# M.net
KiCad netlist of a schematic drawn in Altium Designer
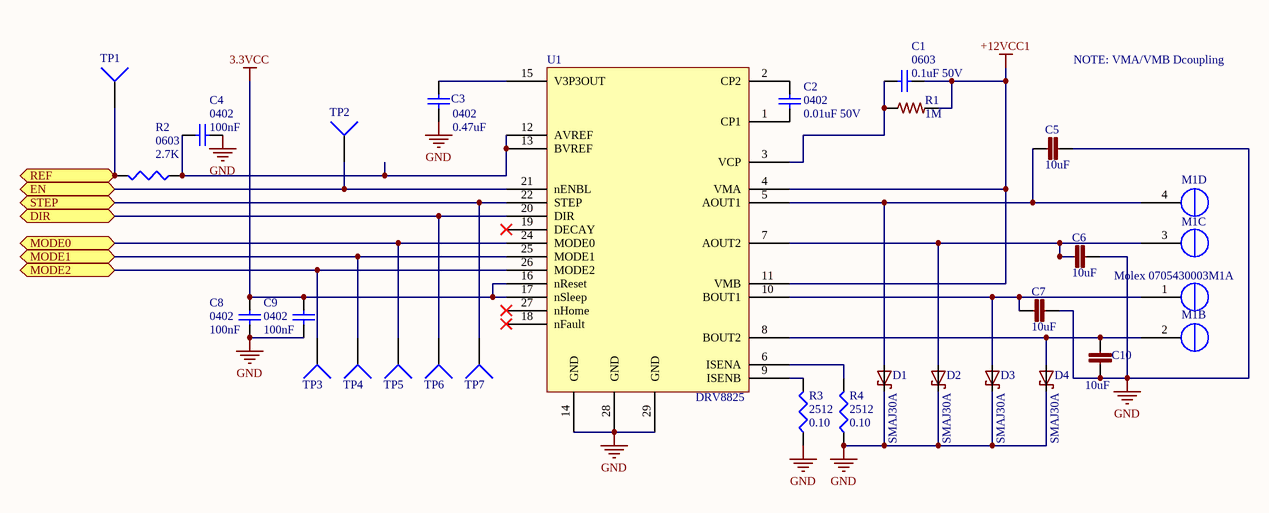
[diagram p0: M.SchDoc]

(export (version "E")
  (design (tool "Eeschema 10.0.6"))
  (components
    (comp (ref "C1")
      (value "0603")
      (footprint "1608[0603]")
      (description "Capacitor (Semiconductor SIM Model)")
      (fields (field (name "ALTIUM_VALUE") "0.1uF 50V") (field (name "PUBLISHER") "Altium Limited"))
      (libsource (lib "Miscellaneous Devices") (part "Cap Semi"))
    )
    (comp (ref "C2")
      (value "0.01uF 50V")
      (footprint "C0402")
      (description "CAP CER 10000PF 50V X7R 0402")
      (fields
        (field (name "MFR PART #") "GRM155R71H103JA88D")
        (field (name "MFR") "Murata")
        (field (name "PACKAGEREFERENCE") "0402")
        (field (name "PUBLISHER") "Ultimachine")
      )
      (libsource (lib "Tigershark3D") (part "GRM155R71H103JA88D"))
    )
    (comp (ref "C3")
      (value "0.47uF")
      (footprint "C0402")
      (description "0.47uF 6.3v C0402 - GRM155R60J474KE19D")
      (fields
        (field (name "MFR PART #") "GRM155R60J474KE19D")
        (field (name "MFR") "Murata")
        (field (name "PACKAGEREFERENCE") "0402")
        (field (name "PUBLISHER") "Ultimachine")
      )
      (libsource (lib "Tigershark3D") (part "GRM155R60J474KE19D"))
    )
    (comp (ref "C4")
      (value "100nF")
      (footprint "C0402")
      (description "Capacitor (Semiconductor SIM Model)")
      (fields
        (field (name "MFR PART #") "GRM155R71C104KA88D")
        (field (name "MFR") "Murata")
        (field (name "PACKAGEREFERENCE") "0402")
        (field (name "PUBLISHER") "Ultimachine")
      )
      (libsource (lib "Tigershark3D") (part "100nF C0402 - GRM155R71C104KA88D"))
    )
    (comp (ref "C5")
      (value "10uF")
      (footprint "C0603")
      (description "CAP CER 0603 1uF 10V Y5V")
      (fields
        (field (name "MANUFACTURERPARTNUMBER") "CC0603ZRY5V6BB105")
        (field (name "PUBLISHER") "UltiMachine")
      )
      (libsource (lib "Tigershark3D") (part "CC0603ZRY5V6BB105"))
    )
    (comp (ref "C6")
      (value "10uF")
      (footprint "C0603")
      (description "CAP CER 0603 1uF 10V Y5V")
      (fields
        (field (name "MANUFACTURERPARTNUMBER") "CC0603ZRY5V6BB105")
        (field (name "PUBLISHER") "UltiMachine")
      )
      (libsource (lib "Tigershark3D") (part "CC0603ZRY5V6BB105"))
    )
    (comp (ref "C7")
      (value "10uF")
      (footprint "C0603")
      (description "CAP CER 0603 1uF 10V Y5V")
      (fields
        (field (name "MANUFACTURERPARTNUMBER") "CC0603ZRY5V6BB105")
        (field (name "PUBLISHER") "UltiMachine")
      )
      (libsource (lib "Tigershark3D") (part "CC0603ZRY5V6BB105"))
    )
    (comp (ref "C8")
      (value "100nF")
      (footprint "C0402")
      (description "Capacitor (Semiconductor SIM Model)")
      (fields
        (field (name "MFR PART #") "GRM155R71C104KA88D")
        (field (name "MFR") "Murata")
        (field (name "PACKAGEREFERENCE") "0402")
        (field (name "PUBLISHER") "Ultimachine")
      )
      (libsource (lib "Tigershark3D") (part "100nF C0402 - GRM155R71C104KA88D"))
    )
    (comp (ref "C9")
      (value "100nF")
      (footprint "C0402")
      (description "Capacitor (Semiconductor SIM Model)")
      (fields
        (field (name "MFR PART #") "GRM155R71C104KA88D")
        (field (name "MFR") "Murata")
        (field (name "PACKAGEREFERENCE") "0402")
        (field (name "PUBLISHER") "Ultimachine")
      )
      (libsource (lib "Tigershark3D") (part "100nF C0402 - GRM155R71C104KA88D"))
    )
    (comp (ref "C10")
      (value "10uF")
      (footprint "C0603")
      (description "CAP CER 0603 1uF 10V Y5V")
      (fields
        (field (name "MANUFACTURERPARTNUMBER") "CC0603ZRY5V6BB105")
        (field (name "PUBLISHER") "UltiMachine")
      )
      (libsource (lib "") (part "CC0603ZRY5V6BB105_1"))
    )
    (comp (ref "D1")
      (value "SMAJ30A")
      (footprint "SMA-SM")
      (description "DIODE TVS 30V SMA")
      (fields (field (name "PUBLISHER") "UltiMachine"))
      (libsource (lib "Tigershark3D") (part "SMAJ30A"))
    )
    (comp (ref "D2")
      (value "SMAJ30A")
      (footprint "SMA-SM")
      (description "DIODE TVS 30V SMA")
      (fields (field (name "PUBLISHER") "UltiMachine"))
      (libsource (lib "Tigershark3D") (part "SMAJ30A"))
    )
    (comp (ref "D3")
      (value "SMAJ30A")
      (footprint "SMA-SM")
      (description "DIODE TVS 30V SMA")
      (fields (field (name "PUBLISHER") "UltiMachine"))
      (libsource (lib "Tigershark3D") (part "SMAJ30A"))
    )
    (comp (ref "D4")
      (value "SMAJ30A")
      (footprint "SMA-SM")
      (description "DIODE TVS 30V SMA")
      (fields (field (name "PUBLISHER") "UltiMachine"))
      (libsource (lib "Tigershark3D") (part "SMAJ30A"))
    )
    (comp (ref "M1")
      (value "Molex 0705430003")
      (footprint "4POL254")
      (description "Molex 4 Pin Clip Connector")
      (libsource (lib "ZMBo Schematic Library") (part "Molex 0705430003 Alt"))
    )
    (comp (ref "R1")
      (value "1M")
      (footprint "R0402")
      (description "RES 0402 1M 100mW 5%")
      (fields (field (name "MANUFACTURERPARTNUMBER") "ERJ2GEJ105X") (field (name "PUBLISHER") "UltiMachine"))
      (libsource (lib "Tigershark3D") (part "ERJ2GEJ105X"))
    )
    (comp (ref "R2")
      (value "0603")
      (footprint "J1-0603")
      (description "Resistor")
      (fields (field (name "ALTIUM_VALUE") "2.7K") (field (name "PUBLISHER") "Altium Limited"))
      (libsource (lib "Miscellaneous Devices") (part "Res3"))
    )
    (comp (ref "R3")
      (value "2512")
      (footprint "Resistor2512")
      (description "Resistor")
      (fields (field (name "ALTIUM_VALUE") "0.10") (field (name "PUBLISHER") "Altium Limited"))
      (libsource (lib "Miscellaneous Devices") (part "Res3"))
    )
    (comp (ref "R4")
      (value "2512")
      (footprint "Resistor2512")
      (description "Resistor")
      (fields (field (name "ALTIUM_VALUE") "0.10") (field (name "PUBLISHER") "Altium Limited"))
      (libsource (lib "Miscellaneous Devices") (part "Res3"))
    )
    (comp (ref "TP1")
      (value "TP4")
      (footprint "TP-2")
      (description "Socket")
      (fields (field (name "PUBLISHER") "Altium Limited"))
      (libsource (lib "ZMBo Schematic Library") (part "Socket"))
    )
    (comp (ref "TP2")
      (value "TP4")
      (footprint "TP-2")
      (description "Socket")
      (fields (field (name "PUBLISHER") "Altium Limited"))
      (libsource (lib "ZMBo Schematic Library") (part "Socket"))
    )
    (comp (ref "TP3")
      (value "TP4")
      (footprint "TP-2")
      (description "Socket")
      (fields (field (name "PUBLISHER") "Altium Limited"))
      (libsource (lib "ZMBo Schematic Library") (part "Socket"))
    )
    (comp (ref "TP4")
      (value "TP4")
      (footprint "TP-2")
      (description "Socket")
      (fields (field (name "PUBLISHER") "Altium Limited"))
      (libsource (lib "ZMBo Schematic Library") (part "Socket"))
    )
    (comp (ref "TP5")
      (value "TP4")
      (footprint "TP-2")
      (description "Socket")
      (fields (field (name "PUBLISHER") "Altium Limited"))
      (libsource (lib "ZMBo Schematic Library") (part "Socket"))
    )
    (comp (ref "TP6")
      (value "TP4")
      (footprint "TP-2")
      (description "Socket")
      (fields (field (name "PUBLISHER") "Altium Limited"))
      (libsource (lib "ZMBo Schematic Library") (part "Socket"))
    )
    (comp (ref "TP7")
      (value "TP4")
      (footprint "TP-2")
      (description "Socket")
      (fields (field (name "PUBLISHER") "Altium Limited"))
      (libsource (lib "ZMBo Schematic Library") (part "Socket"))
    )
    (comp (ref "U1")
      (value "DRV8825")
      (footprint "DRV8825")
      (description "DRV8825 Ti Stepper Driver")
      (libsource (lib "ZMBo Schematic Library") (part "DRV8825"))
    )
  )
  (nets
    (net (code "1") (name "+12VCC1") (class "Default")
      (node (ref "C1") (pin "1") (pinfunction "1_1") (pintype "passive"))
      (node (ref "R1") (pin "2") (pinfunction "2_2") (pintype "passive"))
      (node (ref "U1") (pin "11") (pinfunction "VMB_11") (pintype "passive"))
      (node (ref "U1") (pin "4") (pinfunction "VMA_4") (pintype "passive"))
    )
    (net (code "2") (name "/DIR") (class "Default")
      (node (ref "TP6") (pin "1") (pinfunction "1_1") (pintype "passive"))
      (node (ref "U1") (pin "20") (pinfunction "DIR_20") (pintype "passive"))
    )
    (net (code "3") (name "/EN") (class "Default")
      (node (ref "TP2") (pin "1") (pinfunction "1_1") (pintype "passive"))
      (node (ref "U1") (pin "21") (pinfunction "nENBL_21") (pintype "passive"))
    )
    (net (code "4") (name "/MODE0") (class "Default")
      (node (ref "TP5") (pin "1") (pinfunction "1_1") (pintype "passive"))
      (node (ref "U1") (pin "24") (pinfunction "MODE0_24") (pintype "passive"))
    )
    (net (code "5") (name "/MODE1") (class "Default")
      (node (ref "TP4") (pin "1") (pinfunction "1_1") (pintype "passive"))
      (node (ref "U1") (pin "25") (pinfunction "MODE1_25") (pintype "passive"))
    )
    (net (code "6") (name "/MODE2") (class "Default")
      (node (ref "TP3") (pin "1") (pinfunction "1_1") (pintype "passive"))
      (node (ref "U1") (pin "26") (pinfunction "MODE2_26") (pintype "passive"))
    )
    (net (code "7") (name "/REF") (class "Default")
      (node (ref "R2") (pin "2") (pinfunction "2_2") (pintype "passive"))
      (node (ref "TP1") (pin "1") (pinfunction "1_1") (pintype "passive"))
    )
    (net (code "8") (name "/STEP") (class "Default")
      (node (ref "TP7") (pin "1") (pinfunction "1_1") (pintype "passive"))
      (node (ref "U1") (pin "22") (pinfunction "STEP_22") (pintype "passive"))
    )
    (net (code "9") (name "3.3VCC") (class "Default")
      (node (ref "C8") (pin "2") (pinfunction "2_2") (pintype "passive"))
      (node (ref "C9") (pin "2") (pinfunction "2_2") (pintype "passive"))
      (node (ref "U1") (pin "16") (pinfunction "nReset_16") (pintype "passive"))
      (node (ref "U1") (pin "17") (pinfunction "nSleep_17") (pintype "passive"))
    )
    (net (code "10") (name "GND") (class "Default")
      (node (ref "C10") (pin "2") (pinfunction "2_2") (pintype "passive"))
      (node (ref "C3") (pin "1") (pinfunction "1_1") (pintype "passive"))
      (node (ref "C4") (pin "1") (pinfunction "1_1") (pintype "passive"))
      (node (ref "C5") (pin "2") (pinfunction "2_2") (pintype "passive"))
      (node (ref "C6") (pin "2") (pinfunction "2_2") (pintype "passive"))
      (node (ref "C7") (pin "2") (pinfunction "2_2") (pintype "passive"))
      (node (ref "C8") (pin "1") (pinfunction "1_1") (pintype "passive"))
      (node (ref "C9") (pin "1") (pinfunction "1_1") (pintype "passive"))
      (node (ref "D1") (pin "C") (pinfunction "C_C") (pintype "passive"))
      (node (ref "D2") (pin "C") (pinfunction "C_C") (pintype "passive"))
      (node (ref "D3") (pin "C") (pinfunction "C_C") (pintype "passive"))
      (node (ref "D4") (pin "C") (pinfunction "C_C") (pintype "passive"))
      (node (ref "R3") (pin "1") (pinfunction "1_1") (pintype "passive"))
      (node (ref "R4") (pin "1") (pinfunction "1_1") (pintype "passive"))
      (node (ref "U1") (pin "14") (pinfunction "GND_14") (pintype "passive"))
      (node (ref "U1") (pin "28") (pinfunction "GND_28") (pintype "passive"))
      (node (ref "U1") (pin "29") (pinfunction "GND_29") (pintype "passive"))
    )
    (net (code "11") (name "Net-(M1A-OUT2B)") (class "Default")
      (node (ref "C7") (pin "1") (pinfunction "1_1") (pintype "passive"))
      (node (ref "D3") (pin "A") (pinfunction "A_A") (pintype "passive"))
      (node (ref "M1") (pin "1") (pinfunction "OUT2B_1") (pintype "passive"))
      (node (ref "U1") (pin "10") (pinfunction "BOUT1_10") (pintype "passive"))
    )
    (net (code "12") (name "Net-(M1B-OUT2A)") (class "Default")
      (node (ref "C10") (pin "1") (pinfunction "1_1") (pintype "passive"))
      (node (ref "D4") (pin "A") (pinfunction "A_A") (pintype "passive"))
      (node (ref "M1") (pin "2") (pinfunction "OUT2A_2") (pintype "passive"))
      (node (ref "U1") (pin "8") (pinfunction "BOUT2_8") (pintype "passive"))
    )
    (net (code "13") (name "Net-(M1C-OUT1A)") (class "Default")
      (node (ref "C6") (pin "1") (pinfunction "1_1") (pintype "passive"))
      (node (ref "D2") (pin "A") (pinfunction "A_A") (pintype "passive"))
      (node (ref "M1") (pin "3") (pinfunction "OUT1A_3") (pintype "passive"))
      (node (ref "U1") (pin "7") (pinfunction "AOUT2_7") (pintype "passive"))
    )
    (net (code "14") (name "Net-(M1D-OUT1B)") (class "Default")
      (node (ref "C5") (pin "1") (pinfunction "1_1") (pintype "passive"))
      (node (ref "D1") (pin "A") (pinfunction "A_A") (pintype "passive"))
      (node (ref "M1") (pin "4") (pinfunction "OUT1B_4") (pintype "passive"))
      (node (ref "U1") (pin "5") (pinfunction "AOUT1_5") (pintype "passive"))
    )
    (net (code "15") (name "Net-(U1-AVREF)") (class "Default")
      (node (ref "C4") (pin "2") (pinfunction "2_2") (pintype "passive"))
      (node (ref "R2") (pin "1") (pinfunction "1_1") (pintype "passive"))
      (node (ref "U1") (pin "12") (pinfunction "AVREF_12") (pintype "passive"))
      (node (ref "U1") (pin "13") (pinfunction "BVREF_13") (pintype "passive"))
    )
    (net (code "16") (name "Net-(U1-CP1)") (class "Default")
      (node (ref "C2") (pin "1") (pinfunction "1_1") (pintype "passive"))
      (node (ref "U1") (pin "1") (pinfunction "CP1_1") (pintype "passive"))
    )
    (net (code "17") (name "Net-(U1-CP2)") (class "Default")
      (node (ref "C2") (pin "2") (pinfunction "2_2") (pintype "passive"))
      (node (ref "U1") (pin "2") (pinfunction "CP2_2") (pintype "passive"))
    )
    (net (code "18") (name "Net-(U1-ISENA)") (class "Default")
      (node (ref "R4") (pin "2") (pinfunction "2_2") (pintype "passive"))
      (node (ref "U1") (pin "6") (pinfunction "ISENA_6") (pintype "passive"))
    )
    (net (code "19") (name "Net-(U1-ISENB)") (class "Default")
      (node (ref "R3") (pin "2") (pinfunction "2_2") (pintype "passive"))
      (node (ref "U1") (pin "9") (pinfunction "ISENB_9") (pintype "passive"))
    )
    (net (code "20") (name "Net-(U1-V3P3OUT)") (class "Default")
      (node (ref "C3") (pin "2") (pinfunction "2_2") (pintype "passive"))
      (node (ref "U1") (pin "15") (pinfunction "V3P3OUT_15") (pintype "passive"))
    )
    (net (code "21") (name "Net-(U1-VCP)") (class "Default")
      (node (ref "C1") (pin "2") (pinfunction "2_2") (pintype "passive"))
      (node (ref "R1") (pin "1") (pinfunction "1_1") (pintype "passive"))
      (node (ref "U1") (pin "3") (pinfunction "VCP_3") (pintype "passive"))
    )
    (net (code "22") (name "unconnected-(U1-DECAY-Pad19)") (class "Default")
      (node (ref "U1") (pin "19") (pinfunction "DECAY_19") (pintype "passive+no_connect"))
    )
    (net (code "23") (name "unconnected-(U1-NC-Pad23)") (class "Default")
      (node (ref "U1") (pin "23") (pinfunction "NC_23") (pintype "passive"))
    )
    (net (code "24") (name "unconnected-(U1-nFault-Pad18)") (class "Default")
      (node (ref "U1") (pin "18") (pinfunction "nFault_18") (pintype "passive+no_connect"))
    )
    (net (code "25") (name "unconnected-(U1-nHome-Pad27)") (class "Default")
      (node (ref "U1") (pin "27") (pinfunction "nHome_27") (pintype "passive+no_connect"))
    )
  )
)
